# Power_Sheet.net
KiCad netlist of a schematic drawn in Altium Designer
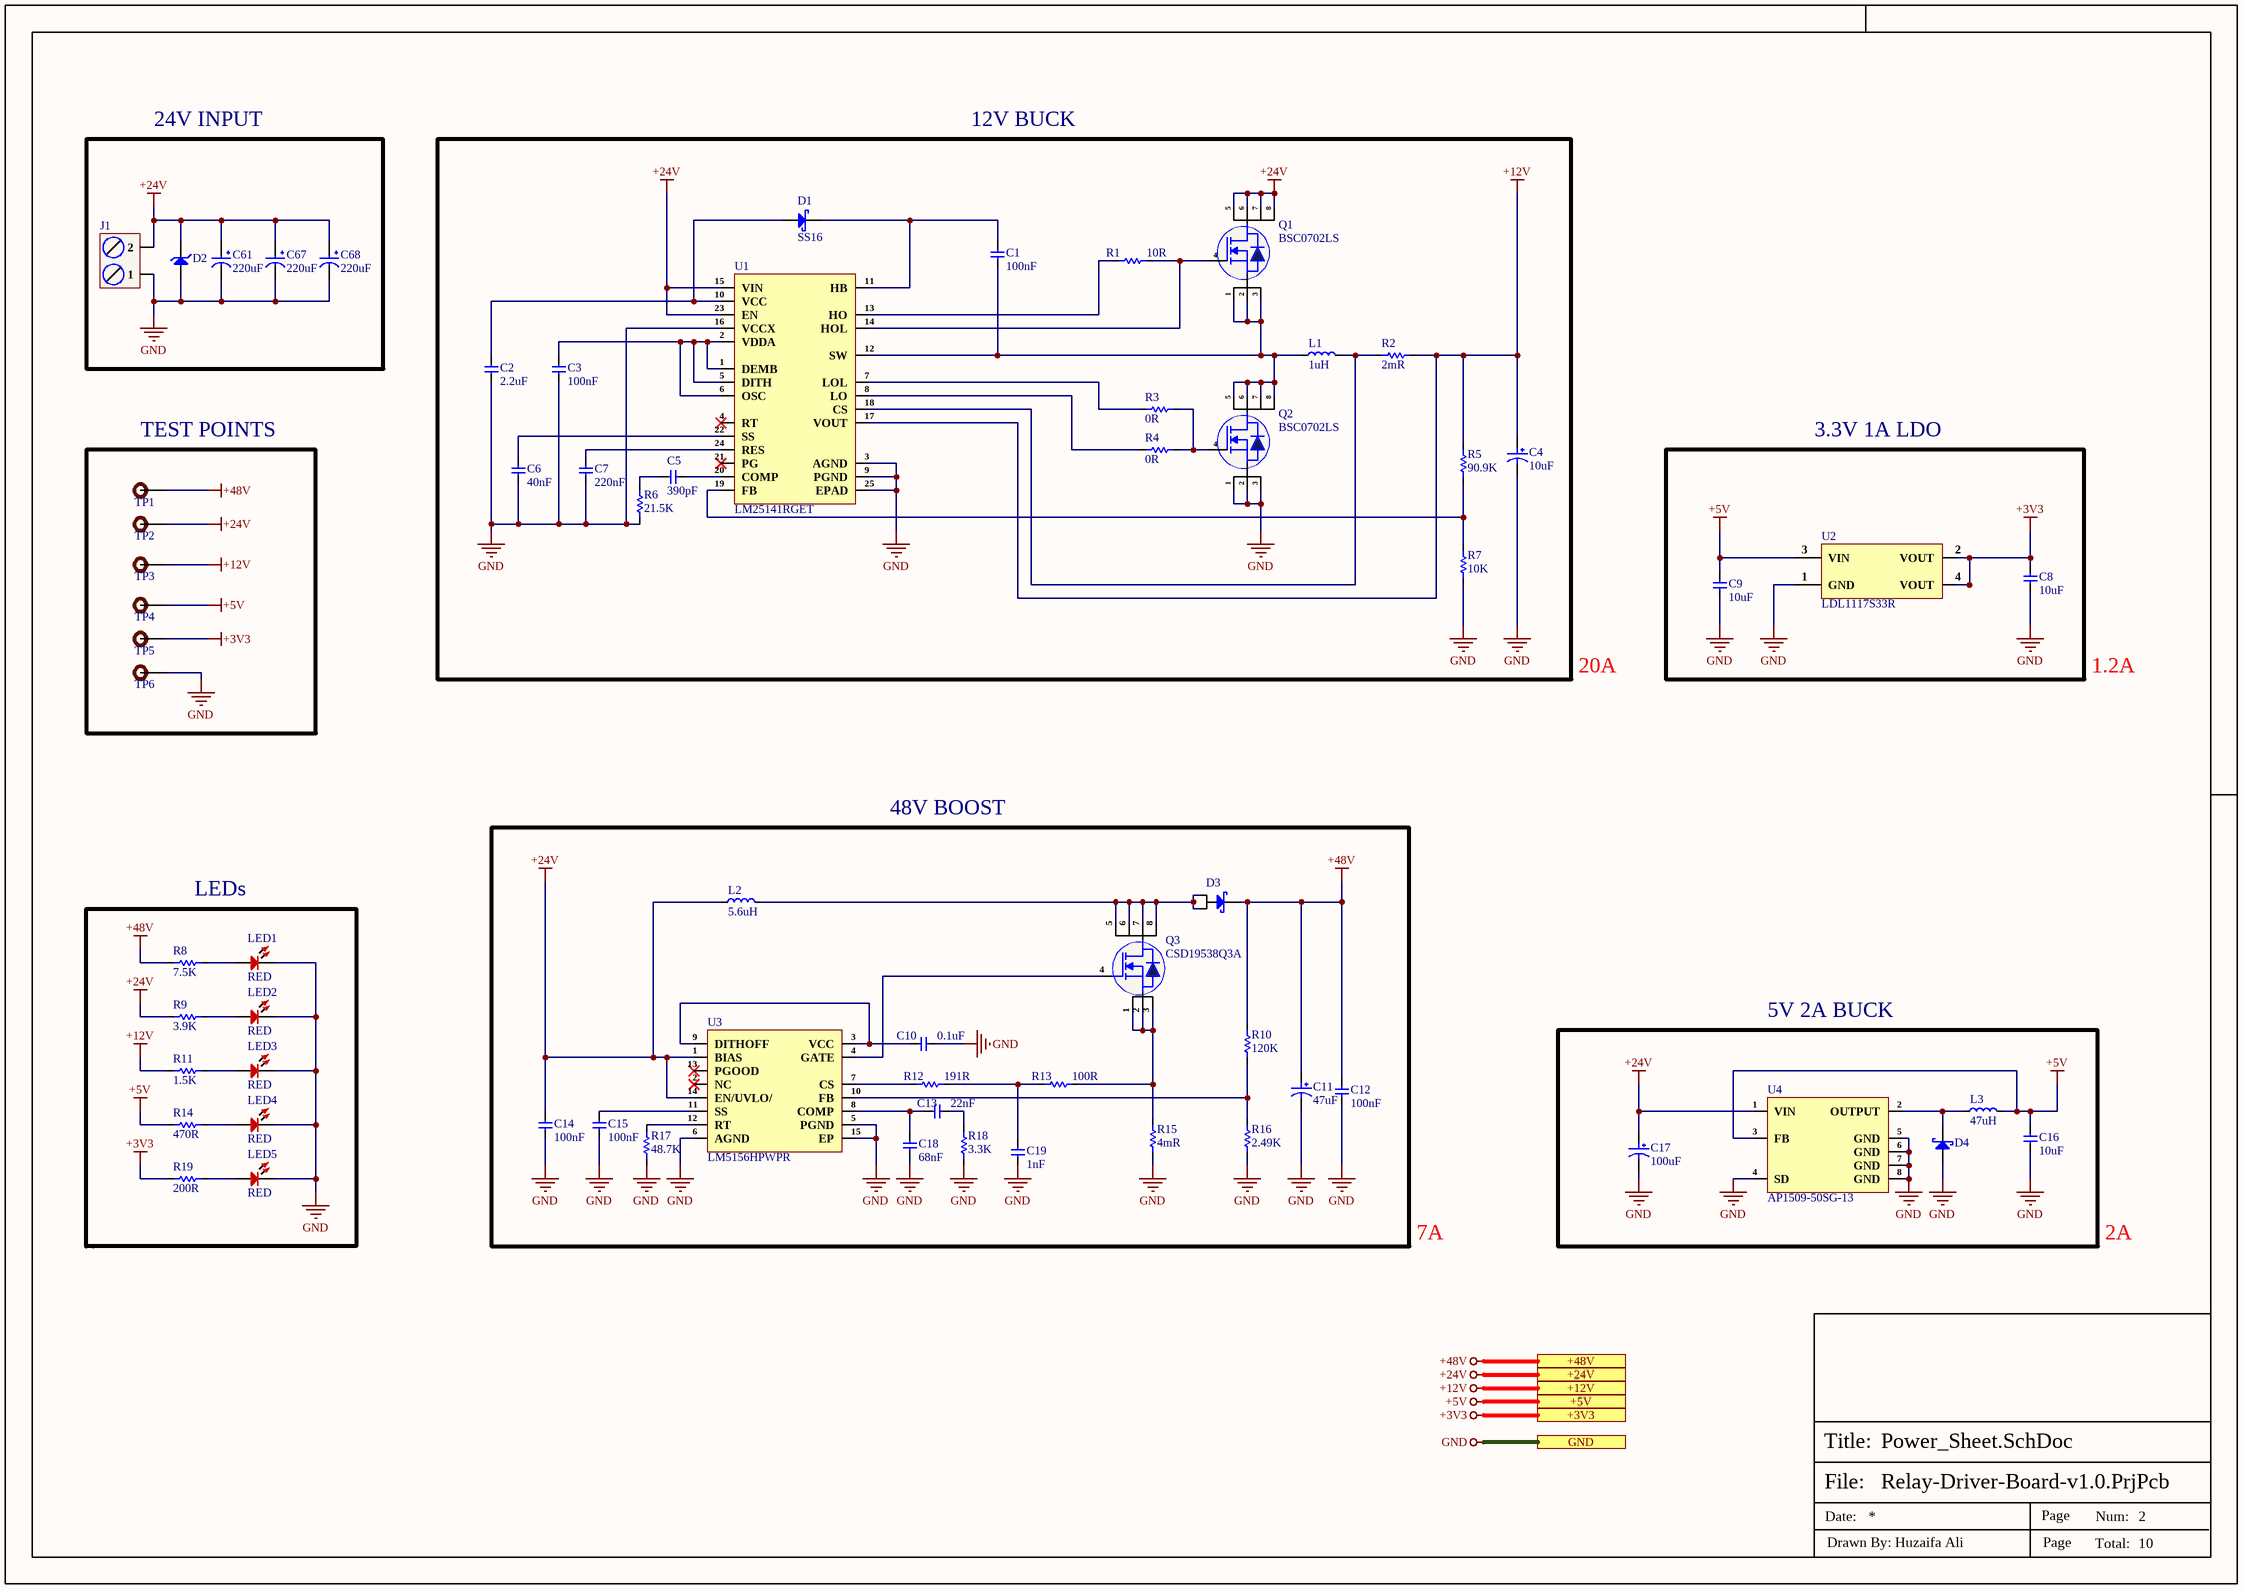
[diagram p0: Power_Sheet.SchDoc]

(export (version "E")
  (design (tool "Eeschema 10.0.6"))
  (components
    (comp (ref "C1")
      (value "100nF")
      (footprint "cap-0402")
      (description "CAP CER 0.1UF 50V X7R 0402")
      (fields
        (field (name "MANUFACTURER") "TDK")
        (field (name "MANUFACTURER PART NUMBER") "C1005X7R1H104KT000F")
      )
      (libsource (lib "eSpark Libraries") (part "C1005X7R1H104KT000F"))
    )
    (comp (ref "C2")
      (value "2.2uF")
      (footprint "Cap-0805")
      (description "CAP CER 2.2UF 50V X5R 0805")
      (fields
        (field (name "MANUFACTURER") "TDK")
        (field (name "MANUFACTURER PART NUMBER") "C2012X5R1H225K125AB")
      )
      (libsource (lib "eSpark Libraries") (part "C2012X5R1H225K125AB"))
    )
    (comp (ref "C3")
      (value "100nF")
      (footprint "cap-0402")
      (description "CAP CER 0.1UF 50V X7R 0402")
      (fields
        (field (name "MANUFACTURER") "TDK")
        (field (name "MANUFACTURER PART NUMBER") "C1005X7R1H104KT000F")
      )
      (libsource (lib "eSpark Libraries") (part "C1005X7R1H104KT000F"))
    )
    (comp (ref "C4")
      (value "10uF")
      (footprint "50SVPF10M")
      (description "CAP ALUM POLY 10UF 20% 50V SMD")
      (fields (field (name "MANUFACTURER") "Panasonic") (field (name "MANUFACTURER PART NUMBER") "50SVPF10M"))
      (libsource (lib "eSpark Libraries") (part "50SVPF10M"))
    )
    (comp (ref "C5")
      (value "390pF")
      (footprint "Cap-0402")
      (description "CAP CER 390PF 50V C0G 0402")
      (fields
        (field (name "MANUFACTURER") "TDK")
        (field (name "MANUFACTURER PART NUMBER") "CGA2B2C0G1H391J050BA")
      )
      (libsource (lib "eSpark Libraries") (part "CGA2B2C0G1H391J050BA"))
    )
    (comp (ref "C6")
      (value "40nF")
      (footprint "Cap-0805")
      (description "50V 40nF Y5V ±20% 0805 Multilayer Ceramic Capacitors MLCC - SMD/SMT ROHS")
      (fields
        (field (name "MANUFACTURER") "FH (Guangdong Fenghua Advanced Tech)")
        (field (name "MANUFACTURER PART NUMBER") "0805F403M500NT")
      )
      (libsource (lib "eSpark Libraries") (part "0805F403M500NT"))
    )
    (comp (ref "C7")
      (value "220nF")
      (footprint "Cap-0402")
      (description "CAP CER 0.22UF 25V X5R 0402")
      (fields
        (field (name "MANUFACTURER") "Yageo")
        (field (name "MANUFACTURER PART NUMBER") "CC0402KRX5R8BB224")
      )
      (libsource (lib "eSpark Libraries") (part "CC0402KRX5R8BB224"))
    )
    (comp (ref "C8")
      (value "10uF")
      (footprint "Cap-0603")
      (description "CAP CER 10UF 25V X5R 0603")
      (fields
        (field (name "MANUFACTURER") "TDK")
        (field (name "MANUFACTURER PART NUMBER") "C1608X5R1E106M080AC")
      )
      (libsource (lib "eSpark Libraries") (part "C1608X5R1E106M080AC"))
    )
    (comp (ref "C9")
      (value "10uF")
      (footprint "Cap-0603")
      (description "CAP CER 10UF 25V X5R 0603")
      (fields
        (field (name "MANUFACTURER") "TDK")
        (field (name "MANUFACTURER PART NUMBER") "C1608X5R1E106M080AC")
      )
      (libsource (lib "eSpark Libraries") (part "C1608X5R1E106M080AC"))
    )
    (comp (ref "C10")
      (value "0.1uF")
      (footprint "Cap-0402")
      (description "CAP CER 0.1UF 16V X7R 0402")
      (fields
        (field (name "MANUFACTURER") "Yageo")
        (field (name "MANUFACTURER PART NUMBER") "CC0402JRX7R7BB104")
      )
      (libsource (lib "eSpark Libraries") (part "CC0402JRX7R7BB104"))
    )
    (comp (ref "C11")
      (value "47uF")
      (footprint "25SVPF47M")
      (description "CAP ALUM POLY 47UF 20% 25V SMD")
      (fields (field (name "MANUFACTURER") "Panasonic") (field (name "MANUFACTURER PART NUMBER") "25SVPF47M"))
      (libsource (lib "eSpark Libraries") (part "25SVPF47M"))
    )
    (comp (ref "C12")
      (value "100nF")
      (footprint "cap-0402")
      (description "CAP CER 0.1UF 50V X7R 0402")
      (fields
        (field (name "MANUFACTURER") "TDK")
        (field (name "MANUFACTURER PART NUMBER") "C1005X7R1H104KT000F")
      )
      (libsource (lib "eSpark Libraries") (part "C1005X7R1H104KT000F"))
    )
    (comp (ref "C13")
      (value "22nF")
      (footprint "Cap-0402")
      (description "CAP CER 0.022UF 16V X7R 0402")
      (fields
        (field (name "MANUFACTURER") "Yageo")
        (field (name "MANUFACTURER PART NUMBER") "CC0402JRX7R7BB223")
      )
      (libsource (lib "eSpark Libraries") (part "CC0402JRX7R7BB223"))
    )
    (comp (ref "C14")
      (value "100nF")
      (footprint "cap-0402")
      (description "CAP CER 0.1UF 50V X7R 0402")
      (fields
        (field (name "MANUFACTURER") "TDK")
        (field (name "MANUFACTURER PART NUMBER") "C1005X7R1H104KT000F")
      )
      (libsource (lib "eSpark Libraries") (part "C1005X7R1H104KT000F"))
    )
    (comp (ref "C15")
      (value "100nF")
      (footprint "cap-0402")
      (description "CAP CER 0.1UF 50V X7R 0402")
      (fields
        (field (name "MANUFACTURER") "TDK")
        (field (name "MANUFACTURER PART NUMBER") "C1005X7R1H104KT000F")
      )
      (libsource (lib "eSpark Libraries") (part "C1005X7R1H104KT000F"))
    )
    (comp (ref "C16")
      (value "10uF")
      (footprint "Cap-0603")
      (description "CAP CER 10UF 25V X5R 0603")
      (fields
        (field (name "MANUFACTURER") "TDK")
        (field (name "MANUFACTURER PART NUMBER") "C1608X5R1E106M080AC")
      )
      (libsource (lib "eSpark Libraries") (part "C1608X5R1E106M080AC"))
    )
    (comp (ref "C17")
      (value "100uF")
      (footprint "RVT1A101M0605")
      (description "100uF 10V 55mA@120Hz ±20% SMD,D6.3xL5.4mm Aluminum Electrolytic Capacitors - SMD ROHS")
      (fields
        (field (name "MANUFACTURER") "ROQANG")
        (field (name "MANUFACTURER PART NUMBER") "RVT1A101M0605")
      )
      (libsource (lib "eSpark Libraries") (part "RVT1A101M0605"))
    )
    (comp (ref "C18")
      (value "68nF")
      (footprint "Cap-0402")
      (description "CAP CER 0.068UF 50V X7R 0402")
      (fields
        (field (name "MANUFACTURER") "Yageo")
        (field (name "MANUFACTURER PART NUMBER") "CC0402KRX7R9BB683")
      )
      (libsource (lib "eSpark Libraries") (part "CC0402KRX7R9BB683"))
    )
    (comp (ref "C19")
      (value "1nF")
      (footprint "Cap-0402")
      (description "CAP CER 1000PF 25V C0G 0402")
      (fields
        (field (name "MANUFACTURER") "TDK")
        (field (name "MANUFACTURER PART NUMBER") "C1005C0G1E102JT000F")
      )
      (libsource (lib "eSpark Libraries") (part "C1005C0G1E102JT000F"))
    )
    (comp (ref "C61")
      (value "220uF")
      (footprint "UCD-220uF-10mmDia")
      (description "CAP ALUM 220UF 20% 50V SMD")
      (fields
        (field (name "MANUFACTURER") "Nichicon")
        (field (name "MANUFACTURER PART NUMBER") "UCD1H221MNL1GS")
      )
      (libsource (lib "eSpark Libraries") (part "UCD1H221MNL1GS"))
    )
    (comp (ref "C67")
      (value "220uF")
      (footprint "UCD-220uF-10mmDia")
      (description "CAP ALUM 220UF 20% 50V SMD")
      (fields
        (field (name "MANUFACTURER") "Nichicon")
        (field (name "MANUFACTURER PART NUMBER") "UCD1H221MNL1GS")
      )
      (libsource (lib "eSpark Libraries") (part "UCD1H221MNL1GS"))
    )
    (comp (ref "C68")
      (value "220uF")
      (footprint "UCD-220uF-10mmDia")
      (description "CAP ALUM 220UF 20% 50V SMD")
      (fields
        (field (name "MANUFACTURER") "Nichicon")
        (field (name "MANUFACTURER PART NUMBER") "UCD1H221MNL1GS")
      )
      (libsource (lib "eSpark Libraries") (part "UCD1H221MNL1GS"))
    )
    (comp (ref "D1")
      (value "SS16")
      (footprint "SMA")
      (description "60V 700mV@1A 1A SMA(DO-214AC) Schottky Barrier Diodes (SBD) ROHS")
      (fields (field (name "MANUFACTURER") "MDD") (field (name "LCSC PART NUMBER") "C2481"))
      (libsource (lib "eSpark Libraries") (part "SS16"))
    )
    (comp (ref "D2")
      (value "SMBJ28A-13-F")
      (footprint "SMB_")
      (description "TVS DIODE 28VWM 45.4VC SMB")
      (fields (field (name "MANUFACTURER") "Diodes"))
      (libsource (lib "eSpark Libraries") (part "SMBJ28A-13-F"))
    )
    (comp (ref "D3")
      (value "STPS20M100SG-TR")
      (footprint "D2Pak.")
      (description "DIODE SCHOTTKY 100V 20A D2PAK")
      (fields (field (name "MANUFACTURER") "STMicroelectronics") (field (name "LCSC PART NUMBER") "C969989"))
      (libsource (lib "eSpark Libraries") (part "STPS20M100SG-TR"))
    )
    (comp (ref "D4")
      (value "B150-13-F")
      (footprint "SMA")
      (description "DIODE SCHOTTKY 50V 1A SMA")
      (fields (field (name "MANUFACTURER") "Diodes Incorporated") (field (name "LCSC PART NUMBER") "C134431"))
      (libsource (lib "eSpark Libraries") (part "B150-13-F"))
    )
    (comp (ref "J1")
      (value "MXHB9500-9.5-02P-BK01-Cu-S-A")
      (footprint "MXHB9500-9.5-02P-BK01-Cu-S-A")
      (fields (field (name "MANUFACTURER") "MAX") (field (name "LCSC PART NUMBER") "C7542168"))
      (libsource (lib "eSpark Libraries") (part "MXHB9500-9.5-02P-BK01-Cu-S-A"))
    )
    (comp (ref "L1")
      (value "1uH")
      (description "25.5A 1uH Molding Choke ±20% 37A SMD,13.5x12.5mm Power Inductors ROHS")
      (fields
        (field (name "MANUFACTURER") "FANGCHENG")
        (field (name "MANUFACTURER PART NUMBER") "FCM1250-1R0M-L-S")
      )
      (libsource (lib "eSpark Libraries") (part "FCM1250-1R0M-L-S"))
    )
    (comp (ref "L2")
      (value "5.6uH")
      (footprint "FXL1360-5R6-M")
      (description "18A 5.6uH Integrated molded inductor ±20% 22.5A SMD,12.6x13.5mm Power Inductors ROHS")
      (fields
        (field (name "MANUFACTURER") "cjiang")
        (field (name "MANUFACTURER PART NUMBER") "FXL1360-5R6-M")
      )
      (libsource (lib "eSpark Libraries") (part "FXL1360-5R6-M"))
    )
    (comp (ref "L3")
      (value "47uH")
      (footprint "CYA0650-47UH")
      (description "2A 47uH ±20% 250mΩ SMD,6.6x7.2mm Inductors (SMD) ROHS")
      (fields
        (field (name "MANUFACTURER") "SHOU HAN")
        (field (name "MANUFACTURER PART NUMBER") "CYA0650-47UH")
      )
      (libsource (lib "eSpark Libraries") (part "CYA0650-47UH"))
    )
    (comp (ref "LED1")
      (value "RED")
      (footprint "LED-0603")
      (description "RED LED 0603 Light Emitting Diodes")
      (fields
        (field (name "MANUFACTURER") "Foshan NationStar Optoelectronics")
        (field (name "MANUFACTURER PART NUMBER") "NCD0603R3")
      )
      (libsource (lib "eSpark Libraries") (part "NCD0603R3"))
    )
    (comp (ref "LED2")
      (value "RED")
      (footprint "LED-0603")
      (description "RED LED 0603 Light Emitting Diodes")
      (fields
        (field (name "MANUFACTURER") "Foshan NationStar Optoelectronics")
        (field (name "MANUFACTURER PART NUMBER") "NCD0603R3")
      )
      (libsource (lib "eSpark Libraries") (part "NCD0603R3"))
    )
    (comp (ref "LED3")
      (value "RED")
      (footprint "LED-0603")
      (description "RED LED 0603 Light Emitting Diodes")
      (fields
        (field (name "MANUFACTURER") "Foshan NationStar Optoelectronics")
        (field (name "MANUFACTURER PART NUMBER") "NCD0603R3")
      )
      (libsource (lib "eSpark Libraries") (part "NCD0603R3"))
    )
    (comp (ref "LED4")
      (value "RED")
      (footprint "LED-0603")
      (description "RED LED 0603 Light Emitting Diodes")
      (fields
        (field (name "MANUFACTURER") "Foshan NationStar Optoelectronics")
        (field (name "MANUFACTURER PART NUMBER") "NCD0603R3")
      )
      (libsource (lib "eSpark Libraries") (part "NCD0603R3"))
    )
    (comp (ref "LED5")
      (value "RED")
      (footprint "LED-0603")
      (description "RED LED 0603 Light Emitting Diodes")
      (fields
        (field (name "MANUFACTURER") "Foshan NationStar Optoelectronics")
        (field (name "MANUFACTURER PART NUMBER") "NCD0603R3")
      )
      (libsource (lib "eSpark Libraries") (part "NCD0603R3"))
    )
    (comp (ref "Q1")
      (value "BSC0702LS")
      (footprint "PG-TDSON-8")
      (description "MOSFET N-CH 60V 100A SUPERSO8")
      (fields
        (field (name "MANUFACTURER") "Infineon")
        (field (name "MANUFACTURER PART NUMBER") "BSC0702LSATMA1")
      )
      (libsource (lib "eSpark Libraries") (part "BSC0702LS"))
    )
    (comp (ref "Q2")
      (value "BSC0702LS")
      (footprint "PG-TDSON-8")
      (description "MOSFET N-CH 60V 100A SUPERSO8")
      (fields
        (field (name "MANUFACTURER") "Infineon")
        (field (name "MANUFACTURER PART NUMBER") "BSC0702LSATMA1")
      )
      (libsource (lib "eSpark Libraries") (part "BSC0702LS"))
    )
    (comp (ref "Q3")
      (value "CSD19538Q3A")
      (footprint "VSONP-8(3.1x3.1)")
      (description "MOSFET N-CH 100V 15A 8VSON")
      (fields (field (name "LCSC PART NUMBER") "C478471") (field (name "MANUFACTURER") "Texas Instruments"))
      (libsource (lib "eSpark Libraries") (part "CSD19538Q3A"))
    )
    (comp (ref "R1")
      (value "10R")
      (footprint "Res-0402")
      (description "RES SMD 10 OHM 1% 1/5W 0402")
      (fields
        (field (name "MANUFACTURER") "Vishay Dale")
        (field (name "MANUFACTURER PART NUMBER") "CRCW040210R0FKEDHP")
      )
      (libsource (lib "eSpark Libraries") (part "CRCW040210R0FKEDHP"))
    )
    (comp (ref "R2")
      (value "2mR")
      (footprint "RES 3920")
      (description "6W 2mΩ Surface Mount Shunt ±50ppm/℃ ±1% 3920 Current Sense Resistors / Shunt Resistors ROHS")
      (fields
        (field (name "MANUFACTURER") "Shenzhen Yezhan Elec")
        (field (name "MANUFACTURER PART NUMBER") "ASR-F-5-2F")
      )
      (libsource (lib "eSpark Libraries") (part "ASR-F-5-2F"))
    )
    (comp (ref "R3")
      (value "0R")
      (footprint "Res-0402")
      (description "RES 0 OHM JUMPER 1/16W 0402")
      (fields
        (field (name "MANUFACTURER") "Yageo")
        (field (name "MANUFACTURER PART NUMBER") "RC0402FR-070RL")
      )
      (libsource (lib "eSpark Libraries") (part "RC0402FR-070RL"))
    )
    (comp (ref "R4")
      (value "0R")
      (footprint "Res-0402")
      (description "RES 0 OHM JUMPER 1/16W 0402")
      (fields
        (field (name "MANUFACTURER") "Yageo")
        (field (name "MANUFACTURER PART NUMBER") "RC0402FR-070RL")
      )
      (libsource (lib "eSpark Libraries") (part "RC0402FR-070RL"))
    )
    (comp (ref "R5")
      (value "90.9K")
      (footprint "Res-0402")
      (description "RES SMD 90.9KOHM 0.5% 1/16W 0402")
      (fields (field (name "LCSC PART NUMBER") "C851529") (field (name "MANUFACTURER") "Yageo"))
      (libsource (lib "eSpark Libraries") (part "AT0402DRD0790K9L"))
    )
    (comp (ref "R6")
      (value "21.5K")
      (footprint "Res-0402")
      (description "62.5mW Thick Film Resistors 50V ±100ppm/℃ ±1% 21.5kΩ 0402 Chip Resistor - Surface Mount ROHS")
      (fields (field (name "LCSC PART NUMBER") "C25872") (field (name "MANUFACTURER") "Uniroyal"))
      (libsource (lib "eSpark Libraries") (part "0402WGF2152TCE"))
    )
    (comp (ref "R7")
      (value "10K")
      (footprint "Res-0402")
      (description "RES 10K OHM 1% 1/16W 0402")
      (fields
        (field (name "MANUFACTURER") "Yageo")
        (field (name "MANUFACTURER PART NUMBER") "RC0402FR-0710KL")
      )
      (libsource (lib "eSpark Libraries") (part "RC0402FR-0710KL"))
    )
    (comp (ref "R8")
      (value "7.5K")
      (footprint "Res-0402")
      (description "RES 7.5K OHM 1% 1/16W 0402")
      (fields
        (field (name "MANUFACTURER") "Yageo")
        (field (name "MANUFACTURER PART NUMBER") "RC0402FR-077K5L")
      )
      (libsource (lib "eSpark Libraries") (part "RC0402FR-077K5L"))
    )
    (comp (ref "R9")
      (value "3.9K")
      (footprint "Res-0402")
      (description "RES 3.9K OHM 1% 1/16W 0402")
      (fields
        (field (name "MANUFACTURER") "Yageo")
        (field (name "MANUFACTURER PART NUMBER") "RC0402FR-073K9L")
      )
      (libsource (lib "eSpark Libraries") (part "RC0402FR-073K9L"))
    )
    (comp (ref "R10")
      (value "120K")
      (footprint "Res-0402")
      (description "RES 120K OHM 1% 1/16W 0402")
      (fields
        (field (name "MANUFACTURER") "Yageo")
        (field (name "MANUFACTURER PART NUMBER") "RC0402FR-07120KL")
      )
      (libsource (lib "eSpark Libraries") (part "RC0402FR-07120KL"))
    )
    (comp (ref "R11")
      (value "1.5K")
      (footprint "Res-0402")
      (description "RES 1.5K OHM 1% 1/16W 0402")
      (fields
        (field (name "MANUFACTURER") "Yageo")
        (field (name "MANUFACTURER PART NUMBER") "RC0402FR-071K5L")
      )
      (libsource (lib "eSpark Libraries") (part "RC0402FR-071K5L"))
    )
    (comp (ref "R12")
      (value "191R")
      (footprint "Res-0402")
      (description "62.5mW Thick Film Resistors ±100ppm/℃ ±1% 191Ω 0402 Chip Resistor - Surface Mount ROHS")
      (fields
        (field (name "MANUFACTURER") "FOJAN")
        (field (name "MANUFACTURER PART NUMBER") "FRC0402F1910TS")
      )
      (libsource (lib "eSpark Libraries") (part "FRC0402F1910TS"))
    )
    (comp (ref "R13")
      (value "100R")
      (footprint "Res-0402")
      (description "RES 100 OHM 1% 1/16W 0402")
      (fields
        (field (name "MANUFACTURER") "Yageo")
        (field (name "MANUFACTURER PART NUMBER") "RC0402FR-07100RL")
      )
      (libsource (lib "eSpark Libraries") (part "RC0402FR-07100RL"))
    )
    (comp (ref "R14")
      (value "470R")
      (footprint "Res-0402")
      (description "RES 470 OHM 1% 1/16W 0402")
      (fields
        (field (name "MANUFACTURER") "Yageo")
        (field (name "MANUFACTURER PART NUMBER") "RC0402FR-07470RL")
      )
      (libsource (lib "eSpark Libraries") (part "RC0402FR-07470RL"))
    )
    (comp (ref "R15")
      (value "4mR")
      (footprint "Res-1206")
      (description "1W 4mΩ Current Sensing Resistors ±50ppm/℃ ±1% 1206 Current Sense Resistors / Shunt Resistors ROHS")
      (fields
        (field (name "MANUFACTURER") "FOJAN")
        (field (name "MANUFACTURER PART NUMBER") "FRM121WFR004TM")
      )
      (libsource (lib "eSpark Libraries") (part "FRM121WFR004TM"))
    )
    (comp (ref "R16")
      (value "2.49K")
      (footprint "Res-0402")
      (description "RES 2.49K OHM 1% 1/16W 0402")
      (fields
        (field (name "MANUFACTURER") "Yageo")
        (field (name "MANUFACTURER PART NUMBER") "RC0402FR-072K49L")
      )
      (libsource (lib "eSpark Libraries") (part "RC0402FR-072K49L"))
    )
    (comp (ref "R17")
      (value "48.7K")
      (footprint "Res-0603")
      (description "RES 48.7K OHM 1% 1/10W 0603")
      (fields
        (field (name "MANUFACTURER") "Yageo")
        (field (name "MANUFACTURER PART NUMBER") "RC0603FR-0748K7L")
      )
      (libsource (lib "eSpark Libraries") (part "RC0603FR-0748K7L"))
    )
    (comp (ref "R18")
      (value "3.3K")
      (footprint "Res-0402")
      (description "RES 3.3K OHM 1% 1/16W 0402")
      (fields
        (field (name "MANUFACTURER") "Yageo")
        (field (name "MANUFACTURER PART NUMBER") "RC0402FR-073K3L")
      )
      (libsource (lib "eSpark Libraries") (part "RC0402FR-073K3L"))
    )
    (comp (ref "R19")
      (value "200R")
      (footprint "Res-0402")
      (description "RES 200 OHM 1% 1/16W 0402")
      (fields
        (field (name "MANUFACTURER") "Yageo")
        (field (name "MANUFACTURER PART NUMBER") "RC0402FR-07200RL")
      )
      (libsource (lib "eSpark Libraries") (part "RC0402FR-07200RL"))
    )
    (comp (ref "TP1")
      (value "TEST POINT")
      (footprint "Test-point")
      (description "Test Point ON")
      (libsource (lib "eSpark Libraries") (part "TEST POINT"))
    )
    (comp (ref "TP2")
      (value "TEST POINT")
      (footprint "Test-point")
      (description "Test Point ON")
      (libsource (lib "eSpark Libraries") (part "TEST POINT"))
    )
    (comp (ref "TP3")
      (value "TEST POINT")
      (footprint "Test-point")
      (description "Test Point ON")
      (libsource (lib "eSpark Libraries") (part "TEST POINT"))
    )
    (comp (ref "TP4")
      (value "TEST POINT")
      (footprint "Test-point")
      (description "Test Point ON")
      (libsource (lib "eSpark Libraries") (part "TEST POINT"))
    )
    (comp (ref "TP5")
      (value "TEST POINT")
      (footprint "Test-point")
      (description "Test Point ON")
      (libsource (lib "eSpark Libraries") (part "TEST POINT"))
    )
    (comp (ref "TP6")
      (value "TEST POINT")
      (footprint "Test-point")
      (description "Test Point ON")
      (libsource (lib "eSpark Libraries") (part "TEST POINT"))
    )
    (comp (ref "U1")
      (value "LM25141RGET")
      (footprint "24-WQFN (4x4)")
      (description "LOW VOLTAGE LM5141- SYNC BUCK CO")
      (fields (field (name "LCSC PART NUMBER") "C2658130") (field (name "MANUFACTURER") "Texas Instruments"))
      (libsource (lib "eSpark Libraries") (part "LM25141RGET"))
    )
    (comp (ref "U2")
      (value "LDL1117S33R")
      (footprint "SOT- 223")
      (description "IC REG LINEAR 3.3V 1.2A SOT223")
      (fields (field (name "MANUFACTURER") "STMicroelectronics") (field (name "LCSC PART NUMBER") "C435835"))
      (libsource (lib "eSpark Libraries") (part "LDL1117S33R"))
    )
    (comp (ref "U3")
      (value "LM5156HPWPR")
      (footprint "HTSSOP-14-EP")
      (description "2.2MHZ WIDE INPUT NONSYNCHRONOUS")
      (fields (field (name "LCSC PART NUMBER") "C2867852") (field (name "MANUFACTURER") "Texas Instruments"))
      (libsource (lib "eSpark Libraries") (part "LM5156HPWPR"))
    )
    (comp (ref "U4")
      (value "AP1509-50SG-13")
      (footprint "SOP-8")
      (description "IC REG BUCK 5V 2A 8SOP")
      (fields (field (name "MANUFACTURER") "Diodes") (field (name "LCSC PART NUMBER") "C9984"))
      (libsource (lib "eSpark Libraries") (part "AP1509-50SG-13"))
    )
  )
  (nets
    (net (code "1") (name "+3V3") (class "Default")
      (node (ref "C8") (pin "2") (pinfunction "2_2") (pintype "passive"))
      (node (ref "R19") (pin "1") (pinfunction "1_1") (pintype "passive"))
      (node (ref "TP5") (pin "1") (pinfunction "1_1") (pintype "passive"))
      (node (ref "U2") (pin "2") (pinfunction "VOUT_2") (pintype "passive"))
      (node (ref "U2") (pin "4") (pinfunction "VOUT_4") (pintype "passive"))
    )
    (net (code "2") (name "+5V") (class "Default")
      (node (ref "C16") (pin "2") (pinfunction "2_2") (pintype "passive"))
      (node (ref "C9") (pin "2") (pinfunction "2_2") (pintype "passive"))
      (node (ref "L3") (pin "2") (pinfunction "2_2") (pintype "passive"))
      (node (ref "R14") (pin "1") (pinfunction "1_1") (pintype "passive"))
      (node (ref "TP4") (pin "1") (pinfunction "1_1") (pintype "passive"))
      (node (ref "U2") (pin "3") (pinfunction "VIN_3") (pintype "passive"))
      (node (ref "U4") (pin "3") (pinfunction "FB_3") (pintype "passive"))
    )
    (net (code "3") (name "+12V") (class "Default")
      (node (ref "C4") (pin "1") (pintype "passive"))
      (node (ref "R11") (pin "1") (pinfunction "1_1") (pintype "passive"))
      (node (ref "R2") (pin "2") (pinfunction "2_2") (pintype "passive"))
      (node (ref "R5") (pin "2") (pinfunction "2_2") (pintype "passive"))
      (node (ref "TP3") (pin "1") (pinfunction "1_1") (pintype "passive"))
      (node (ref "U1") (pin "17") (pinfunction "VOUT_17") (pintype "passive"))
    )
    (net (code "4") (name "+24V") (class "Default")
      (node (ref "C14") (pin "2") (pinfunction "2_2") (pintype "passive"))
      (node (ref "C17") (pin "1") (pintype "passive"))
      (node (ref "C61") (pin "1") (pinfunction "1_1") (pintype "passive"))
      (node (ref "C67") (pin "1") (pinfunction "1_1") (pintype "passive"))
      (node (ref "C68") (pin "1") (pinfunction "1_1") (pintype "passive"))
      (node (ref "D2") (pin "2") (pinfunction "K_2") (pintype "passive"))
      (node (ref "J1") (pin "2") (pinfunction "2_2") (pintype "passive"))
      (node (ref "L2") (pin "1") (pinfunction "1_1") (pintype "passive"))
      (node (ref "Q1") (pin "5") (pinfunction "D_5") (pintype "passive"))
      (node (ref "Q1") (pin "6") (pinfunction "D_6") (pintype "passive"))
      (node (ref "Q1") (pin "7") (pinfunction "D_7") (pintype "passive"))
      (node (ref "Q1") (pin "8") (pinfunction "D_8") (pintype "passive"))
      (node (ref "R9") (pin "1") (pinfunction "1_1") (pintype "passive"))
      (node (ref "TP2") (pin "1") (pinfunction "1_1") (pintype "passive"))
      (node (ref "U1") (pin "15") (pinfunction "VIN_15") (pintype "passive"))
      (node (ref "U1") (pin "23") (pinfunction "EN_23") (pintype "passive"))
      (node (ref "U3") (pin "1") (pinfunction "BIAS_1") (pintype "passive"))
      (node (ref "U3") (pin "14") (pinfunction "EN/UVLO/_14") (pintype "passive"))
      (node (ref "U4") (pin "1") (pinfunction "VIN_1") (pintype "passive"))
    )
    (net (code "5") (name "+48V") (class "Default")
      (node (ref "C11") (pin "1") (pintype "passive"))
      (node (ref "C12") (pin "2") (pinfunction "2_2") (pintype "passive"))
      (node (ref "D3") (pin "3") (pinfunction "K_3") (pintype "passive"))
      (node (ref "R10") (pin "2") (pinfunction "2_2") (pintype "passive"))
      (node (ref "R8") (pin "1") (pinfunction "1_1") (pintype "passive"))
      (node (ref "TP1") (pin "1") (pinfunction "1_1") (pintype "passive"))
    )
    (net (code "6") (name "GND") (class "Default")
      (node (ref "C10") (pin "1") (pinfunction "1_1") (pintype "passive"))
      (node (ref "C11") (pin "2") (pintype "passive"))
      (node (ref "C12") (pin "1") (pinfunction "1_1") (pintype "passive"))
      (node (ref "C14") (pin "1") (pinfunction "1_1") (pintype "passive"))
      (node (ref "C15") (pin "1") (pinfunction "1_1") (pintype "passive"))
      (node (ref "C16") (pin "1") (pinfunction "1_1") (pintype "passive"))
      (node (ref "C17") (pin "2") (pintype "passive"))
      (node (ref "C18") (pin "1") (pinfunction "1_1") (pintype "passive"))
      (node (ref "C19") (pin "1") (pinfunction "1_1") (pintype "passive"))
      (node (ref "C2") (pin "1") (pinfunction "1_1") (pintype "passive"))
      (node (ref "C3") (pin "1") (pinfunction "1_1") (pintype "passive"))
      (node (ref "C4") (pin "2") (pintype "passive"))
      (node (ref "C6") (pin "1") (pinfunction "1_1") (pintype "passive"))
      (node (ref "C61") (pin "2") (pinfunction "2_2") (pintype "passive"))
      (node (ref "C67") (pin "2") (pinfunction "2_2") (pintype "passive"))
      (node (ref "C68") (pin "2") (pinfunction "2_2") (pintype "passive"))
      (node (ref "C7") (pin "1") (pinfunction "1_1") (pintype "passive"))
      (node (ref "C8") (pin "1") (pinfunction "1_1") (pintype "passive"))
      (node (ref "C9") (pin "1") (pinfunction "1_1") (pintype "passive"))
      (node (ref "D2") (pin "1") (pinfunction "A_1") (pintype "passive"))
      (node (ref "D4") (pin "2") (pinfunction "A_2") (pintype "passive"))
      (node (ref "J1") (pin "1") (pinfunction "1_1") (pintype "passive"))
      (node (ref "LED1") (pin "2") (pinfunction "2_2") (pintype "passive"))
      (node (ref "LED2") (pin "2") (pinfunction "2_2") (pintype "passive"))
      (node (ref "LED3") (pin "2") (pinfunction "2_2") (pintype "passive"))
      (node (ref "LED4") (pin "2") (pinfunction "2_2") (pintype "passive"))
      (node (ref "LED5") (pin "2") (pinfunction "2_2") (pintype "passive"))
      (node (ref "Q2") (pin "1") (pinfunction "S_1") (pintype "passive"))
      (node (ref "Q2") (pin "2") (pinfunction "S_2") (pintype "passive"))
      (node (ref "Q2") (pin "3") (pinfunction "S_3") (pintype "passive"))
      (node (ref "R15") (pin "1") (pinfunction "1_1") (pintype "passive"))
      (node (ref "R16") (pin "1") (pinfunction "1_1") (pintype "passive"))
      (node (ref "R17") (pin "1") (pinfunction "1_1") (pintype "passive"))
      (node (ref "R18") (pin "2") (pinfunction "2_2") (pintype "passive"))
      (node (ref "R6") (pin "1") (pinfunction "1_1") (pintype "passive"))
      (node (ref "R7") (pin "1") (pinfunction "1_1") (pintype "passive"))
      (node (ref "TP6") (pin "1") (pinfunction "1_1") (pintype "passive"))
      (node (ref "U1") (pin "16") (pinfunction "VCCX_16") (pintype "passive"))
      (node (ref "U1") (pin "25") (pinfunction "EPAD_25") (pintype "passive"))
      (node (ref "U1") (pin "3") (pinfunction "AGND_3") (pintype "passive"))
      (node (ref "U1") (pin "9") (pinfunction "PGND_9") (pintype "passive"))
      (node (ref "U2") (pin "1") (pinfunction "GND_1") (pintype "passive"))
      (node (ref "U3") (pin "15") (pinfunction "EP_15") (pintype "passive"))
      (node (ref "U3") (pin "5") (pinfunction "PGND_5") (pintype "passive"))
      (node (ref "U3") (pin "6") (pinfunction "AGND_6") (pintype "passive"))
      (node (ref "U4") (pin "4") (pinfunction "SD_4") (pintype "passive"))
      (node (ref "U4") (pin "5") (pinfunction "GND_5") (pintype "passive"))
      (node (ref "U4") (pin "6") (pinfunction "GND_6") (pintype "passive"))
      (node (ref "U4") (pin "7") (pinfunction "GND_7") (pintype "passive"))
      (node (ref "U4") (pin "8") (pinfunction "GND_8") (pintype "passive"))
    )
    (net (code "7") (name "Net-(C5-Pad1)") (class "Default")
      (node (ref "C5") (pin "1") (pinfunction "1_1") (pintype "passive"))
      (node (ref "R6") (pin "2") (pinfunction "2_2") (pintype "passive"))
    )
    (net (code "8") (name "Net-(C13-Pad1)") (class "Default")
      (node (ref "C13") (pin "1") (pinfunction "1_1") (pintype "passive"))
      (node (ref "R18") (pin "1") (pinfunction "1_1") (pintype "passive"))
    )
    (net (code "9") (name "Net-(C19-Pad2)") (class "Default")
      (node (ref "C19") (pin "2") (pinfunction "2_2") (pintype "passive"))
      (node (ref "R12") (pin "2") (pinfunction "2_2") (pintype "passive"))
      (node (ref "R13") (pin "1") (pinfunction "1_1") (pintype "passive"))
    )
    (net (code "10") (name "Net-(D1-A)") (class "Default")
      (node (ref "C2") (pin "2") (pinfunction "2_2") (pintype "passive"))
      (node (ref "D1") (pin "2") (pinfunction "A_2") (pintype "passive"))
      (node (ref "U1") (pin "10") (pinfunction "VCC_10") (pintype "passive"))
    )
    (net (code "11") (name "Net-(D1-K)") (class "Default")
      (node (ref "C1") (pin "2") (pinfunction "2_2") (pintype "passive"))
      (node (ref "D1") (pin "1") (pinfunction "K_1") (pintype "passive"))
      (node (ref "U1") (pin "11") (pinfunction "HB_11") (pintype "passive"))
    )
    (net (code "12") (name "Net-(D3-A-Pad1)") (class "Default")
      (node (ref "D3") (pin "1") (pinfunction "A_1") (pintype "passive"))
      (node (ref "D3") (pin "2") (pinfunction "A_2") (pintype "passive"))
      (node (ref "L2") (pin "2") (pinfunction "2_2") (pintype "passive"))
      (node (ref "Q3") (pin "5") (pinfunction "D_5") (pintype "passive"))
      (node (ref "Q3") (pin "6") (pinfunction "D_6") (pintype "passive"))
      (node (ref "Q3") (pin "7") (pinfunction "D_7") (pintype "passive"))
      (node (ref "Q3") (pin "8") (pinfunction "D_8") (pintype "passive"))
    )
    (net (code "13") (name "Net-(D4-K)") (class "Default")
      (node (ref "D4") (pin "1") (pinfunction "K_1") (pintype "passive"))
      (node (ref "L3") (pin "1") (pinfunction "1_1") (pintype "passive"))
      (node (ref "U4") (pin "2") (pinfunction "OUTPUT_2") (pintype "passive"))
    )
    (net (code "14") (name "Net-(LED1-Pad1)") (class "Default")
      (node (ref "LED1") (pin "1") (pinfunction "1_1") (pintype "passive"))
      (node (ref "R8") (pin "2") (pinfunction "2_2") (pintype "passive"))
    )
    (net (code "15") (name "Net-(LED2-Pad1)") (class "Default")
      (node (ref "LED2") (pin "1") (pinfunction "1_1") (pintype "passive"))
      (node (ref "R9") (pin "2") (pinfunction "2_2") (pintype "passive"))
    )
    (net (code "16") (name "Net-(LED3-Pad1)") (class "Default")
      (node (ref "LED3") (pin "1") (pinfunction "1_1") (pintype "passive"))
      (node (ref "R11") (pin "2") (pinfunction "2_2") (pintype "passive"))
    )
    (net (code "17") (name "Net-(LED4-Pad1)") (class "Default")
      (node (ref "LED4") (pin "1") (pinfunction "1_1") (pintype "passive"))
      (node (ref "R14") (pin "2") (pinfunction "2_2") (pintype "passive"))
    )
    (net (code "18") (name "Net-(LED5-Pad1)") (class "Default")
      (node (ref "LED5") (pin "1") (pinfunction "1_1") (pintype "passive"))
      (node (ref "R19") (pin "2") (pinfunction "2_2") (pintype "passive"))
    )
    (net (code "19") (name "Net-(Q1-G)") (class "Default")
      (node (ref "Q1") (pin "4") (pinfunction "G_4") (pintype "passive"))
      (node (ref "R1") (pin "2") (pinfunction "2_2") (pintype "passive"))
      (node (ref "U1") (pin "14") (pinfunction "HOL_14") (pintype "passive"))
    )
    (net (code "20") (name "Net-(Q2-G)") (class "Default")
      (node (ref "Q2") (pin "4") (pinfunction "G_4") (pintype "passive"))
      (node (ref "R3") (pin "2") (pinfunction "2_2") (pintype "passive"))
      (node (ref "R4") (pin "2") (pinfunction "2_2") (pintype "passive"))
    )
    (net (code "21") (name "Net-(Q3-G)") (class "Default")
      (node (ref "Q3") (pin "4") (pinfunction "G_4") (pintype "passive"))
      (node (ref "U3") (pin "4") (pinfunction "GATE_4") (pintype "passive"))
    )
    (net (code "22") (name "Net-(Q3-S-Pad1)") (class "Default")
      (node (ref "Q3") (pin "1") (pinfunction "S_1") (pintype "passive"))
      (node (ref "Q3") (pin "2") (pinfunction "S_2") (pintype "passive"))
      (node (ref "Q3") (pin "3") (pinfunction "S_3") (pintype "passive"))
      (node (ref "R13") (pin "2") (pinfunction "2_2") (pintype "passive"))
      (node (ref "R15") (pin "2") (pinfunction "2_2") (pintype "passive"))
    )
    (net (code "23") (name "Net-(U1-COMP)") (class "Default")
      (node (ref "C5") (pin "2") (pinfunction "2_2") (pintype "passive"))
      (node (ref "U1") (pin "20") (pinfunction "COMP_20") (pintype "passive"))
    )
    (net (code "24") (name "Net-(U1-CS)") (class "Default")
      (node (ref "L1") (pin "2") (pinfunction "2_2") (pintype "passive"))
      (node (ref "R2") (pin "1") (pinfunction "1_1") (pintype "passive"))
      (node (ref "U1") (pin "18") (pinfunction "CS_18") (pintype "passive"))
    )
    (net (code "25") (name "Net-(U1-DEMB)") (class "Default")
      (node (ref "C3") (pin "2") (pinfunction "2_2") (pintype "passive"))
      (node (ref "U1") (pin "1") (pinfunction "DEMB_1") (pintype "passive"))
      (node (ref "U1") (pin "2") (pinfunction "VDDA_2") (pintype "passive"))
      (node (ref "U1") (pin "5") (pinfunction "DITH_5") (pintype "passive"))
      (node (ref "U1") (pin "6") (pinfunction "OSC_6") (pintype "passive"))
    )
    (net (code "26") (name "Net-(U1-FB)") (class "Default")
      (node (ref "R5") (pin "1") (pinfunction "1_1") (pintype "passive"))
      (node (ref "R7") (pin "2") (pinfunction "2_2") (pintype "passive"))
      (node (ref "U1") (pin "19") (pinfunction "FB_19") (pintype "passive"))
    )
    (net (code "27") (name "Net-(U1-HO)") (class "Default")
      (node (ref "R1") (pin "1") (pinfunction "1_1") (pintype "passive"))
      (node (ref "U1") (pin "13") (pinfunction "HO_13") (pintype "passive"))
    )
    (net (code "28") (name "Net-(U1-LO)") (class "Default")
      (node (ref "R4") (pin "1") (pinfunction "1_1") (pintype "passive"))
      (node (ref "U1") (pin "8") (pinfunction "LO_8") (pintype "passive"))
    )
    (net (code "29") (name "Net-(U1-LOL)") (class "Default")
      (node (ref "R3") (pin "1") (pinfunction "1_1") (pintype "passive"))
      (node (ref "U1") (pin "7") (pinfunction "LOL_7") (pintype "passive"))
    )
    (net (code "30") (name "Net-(U1-RES)") (class "Default")
      (node (ref "C7") (pin "2") (pinfunction "2_2") (pintype "passive"))
      (node (ref "U1") (pin "24") (pinfunction "RES_24") (pintype "passive"))
    )
    (net (code "31") (name "Net-(U1-SS)") (class "Default")
      (node (ref "C6") (pin "2") (pinfunction "2_2") (pintype "passive"))
      (node (ref "U1") (pin "22") (pinfunction "SS_22") (pintype "passive"))
    )
    (net (code "32") (name "Net-(U1-SW)") (class "Default")
      (node (ref "C1") (pin "1") (pinfunction "1_1") (pintype "passive"))
      (node (ref "L1") (pin "1") (pinfunction "1_1") (pintype "passive"))
      (node (ref "Q1") (pin "1") (pinfunction "S_1") (pintype "passive"))
      (node (ref "Q1") (pin "2") (pinfunction "S_2") (pintype "passive"))
      (node (ref "Q1") (pin "3") (pinfunction "S_3") (pintype "passive"))
      (node (ref "Q2") (pin "5") (pinfunction "D_5") (pintype "passive"))
      (node (ref "Q2") (pin "6") (pinfunction "D_6") (pintype "passive"))
      (node (ref "Q2") (pin "7") (pinfunction "D_7") (pintype "passive"))
      (node (ref "Q2") (pin "8") (pinfunction "D_8") (pintype "passive"))
      (node (ref "U1") (pin "12") (pinfunction "SW_12") (pintype "passive"))
    )
    (net (code "33") (name "Net-(U3-COMP)") (class "Default")
      (node (ref "C13") (pin "2") (pinfunction "2_2") (pintype "passive"))
      (node (ref "C18") (pin "2") (pinfunction "2_2") (pintype "passive"))
      (node (ref "U3") (pin "8") (pinfunction "COMP_8") (pintype "passive"))
    )
    (net (code "34") (name "Net-(U3-CS)") (class "Default")
      (node (ref "R12") (pin "1") (pinfunction "1_1") (pintype "passive"))
      (node (ref "U3") (pin "7") (pinfunction "CS_7") (pintype "passive"))
    )
    (net (code "35") (name "Net-(U3-DITHOFF)") (class "Default")
      (node (ref "C10") (pin "2") (pinfunction "2_2") (pintype "passive"))
      (node (ref "U3") (pin "3") (pinfunction "VCC_3") (pintype "passive"))
      (node (ref "U3") (pin "9") (pinfunction "DITHOFF_9") (pintype "passive"))
    )
    (net (code "36") (name "Net-(U3-FB)") (class "Default")
      (node (ref "R10") (pin "1") (pinfunction "1_1") (pintype "passive"))
      (node (ref "R16") (pin "2") (pinfunction "2_2") (pintype "passive"))
      (node (ref "U3") (pin "10") (pinfunction "FB_10") (pintype "passive"))
    )
    (net (code "37") (name "Net-(U3-RT)") (class "Default")
      (node (ref "R17") (pin "2") (pinfunction "2_2") (pintype "passive"))
      (node (ref "U3") (pin "12") (pinfunction "RT_12") (pintype "passive"))
    )
    (net (code "38") (name "Net-(U3-SS)") (class "Default")
      (node (ref "C15") (pin "2") (pinfunction "2_2") (pintype "passive"))
      (node (ref "U3") (pin "11") (pinfunction "SS_11") (pintype "passive"))
    )
    (net (code "39") (name "unconnected-(U1-PG-Pad21)") (class "Default")
      (node (ref "U1") (pin "21") (pinfunction "PG_21") (pintype "passive+no_connect"))
    )
    (net (code "40") (name "unconnected-(U1-RT-Pad4)") (class "Default")
      (node (ref "U1") (pin "4") (pinfunction "RT_4") (pintype "passive+no_connect"))
    )
    (net (code "41") (name "unconnected-(U3-NC-Pad2)") (class "Default")
      (node (ref "U3") (pin "2") (pinfunction "NC_2") (pintype "passive+no_connect"))
    )
    (net (code "42") (name "unconnected-(U3-PGOOD-Pad13)") (class "Default")
      (node (ref "U3") (pin "13") (pinfunction "PGOOD_13") (pintype "passive+no_connect"))
    )
  )
)
